# SAMC21_Xplained_Pro_Arduino_Connectors.net
KiCad netlist of a schematic drawn in Altium Designer
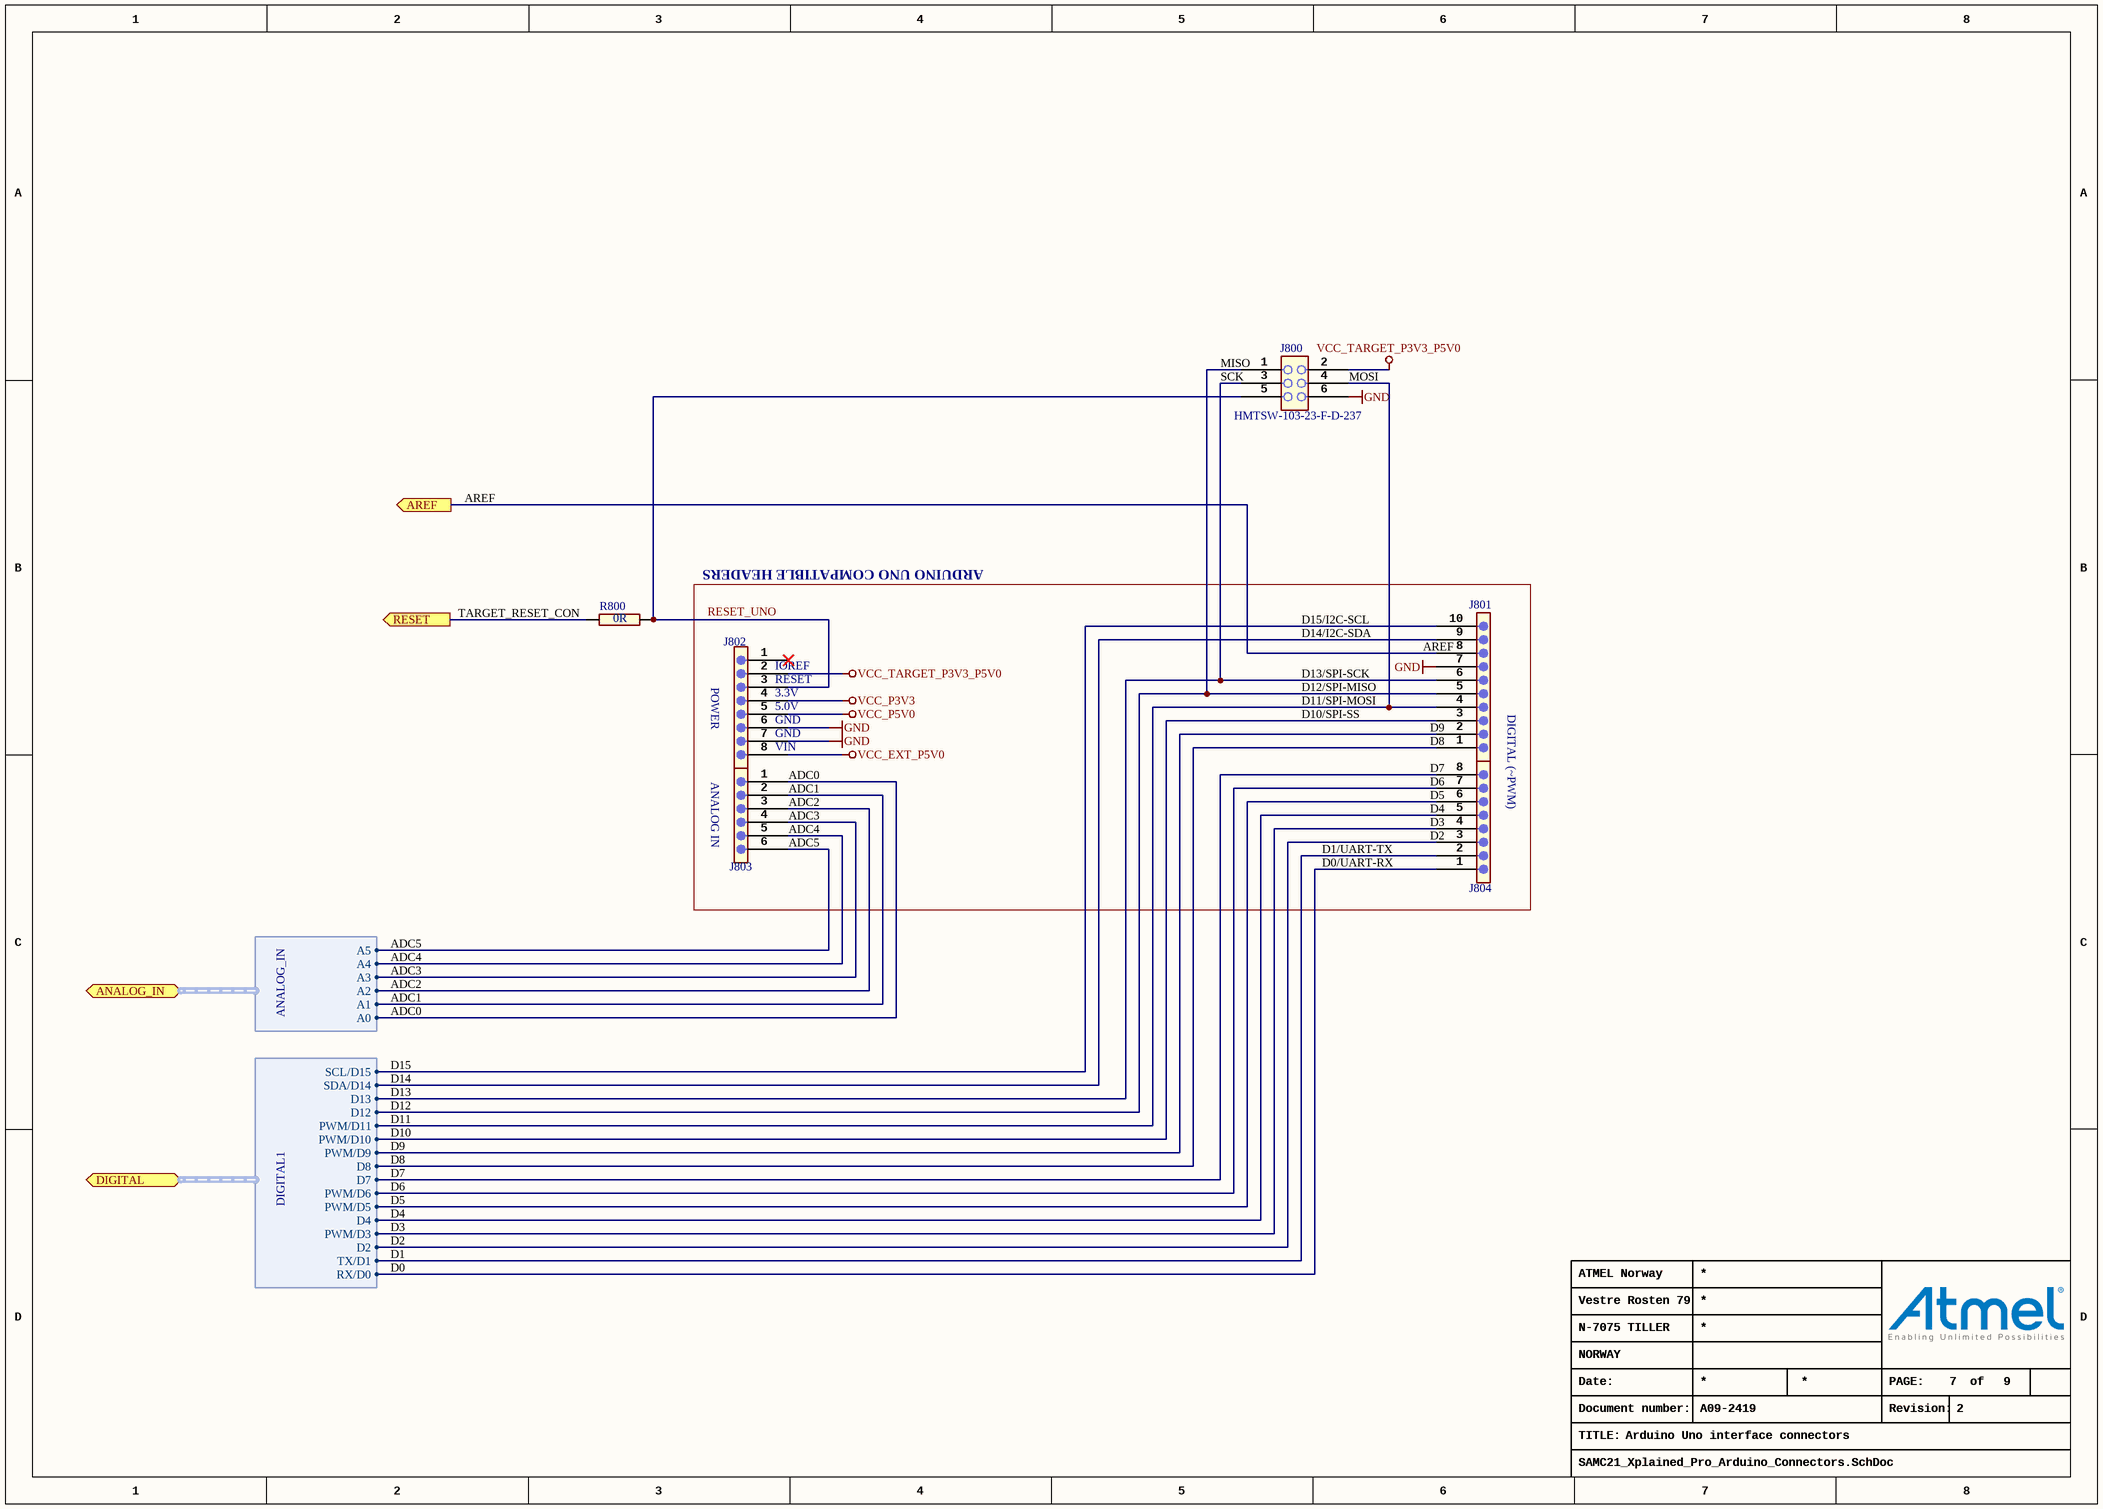
[diagram p0: SAMC21_Xplained_Pro_Arduino_Connectors.SchDoc]

(export (version "E")
  (design (tool "Eeschema 10.0.6"))
  (components
    (comp (ref "J800")
      (value "HMTSW-103-23-F-D-237")
      (footprint "AP8-00182")
      (description "2x3 pin header, 2.54mm pitch, Pin-in-Paste THM")
      (fields (field (name "MANUFACTURER") "SAMTEC") (field (name "Comment") "HEADER 2x3"))
      (libsource (lib "AltiumDbLib") (part "HEADER 2x3"))
    )
    (comp (ref "J801")
      (value "HEADER 1x10 FEMALE")
      (footprint "AP8-00822")
      (description "1x10 receptacle pin header, low insertion force, 2.54mm pitch THM, Pin in Paste")
      (fields (field (name "MANUFACTURER") "SAMTEC") (field (name "MPN") "SSQ-110-21-F-S"))
      (libsource (lib "AltiumDbLib") (part "HEADER 1x10 FEMALE"))
    )
    (comp (ref "J802")
      (value "HEADER 1x8 FEMALE")
      (footprint "AP8-00823")
      (description "1x8 receptacle pin header, low insertion force, 2.54mm pitch THM, Pin in Paste")
      (fields (field (name "MANUFACTURER") "SAMTEC") (field (name "MPN") "SSQ-108-21-F-S"))
      (libsource (lib "AltiumDbLib") (part "HEADER 1x8 FEMALE"))
    )
    (comp (ref "J803")
      (value "HEADER 1x6 FEMALE")
      (footprint "AP8-00824")
      (description "1x6 receptacle pin header, low insertion force, 2.54mm pitch THM")
      (fields (field (name "MANUFACTURER") "SAMTEC") (field (name "MPN") "SSQ-106-21-F-S"))
      (libsource (lib "AltiumDbLib") (part "HEADER 1x6 FEMALE"))
    )
    (comp (ref "J804")
      (value "HEADER 1x8 FEMALE")
      (footprint "AP8-00823")
      (description "1x8 receptacle pin header, low insertion force, 2.54mm pitch THM, Pin in Paste")
      (fields (field (name "MANUFACTURER") "SAMTEC") (field (name "MPN") "SSQ-108-21-F-S"))
      (libsource (lib "") (part "HEADER 1x8 FEMALE_1"))
    )
    (comp (ref "R800")
      (value "0R")
      (footprint "AP2-00000")
      (description "RES 0.0 OHM 1/16W 0402 SMD")
      (fields (field (name "TOLERANCE") "1 %") (field (name "MANUFACTURER") "(n/a)"))
      (libsource (lib "AltiumDbLib") (part "R2"))
    )
  )
  (nets
    (net (code "3") (name "/A0") (class "Default")
      (node (ref "J803") (pin "1") (pinfunction "1_1") (pintype "passive"))
    )
    (net (code "4") (name "/A1") (class "Default")
      (node (ref "J803") (pin "2") (pinfunction "2_2") (pintype "passive"))
    )
    (net (code "5") (name "/A2") (class "Default")
      (node (ref "J803") (pin "3") (pinfunction "3_3") (pintype "passive"))
    )
    (net (code "6") (name "/A3") (class "Default")
      (node (ref "J803") (pin "4") (pinfunction "4_4") (pintype "passive"))
    )
    (net (code "7") (name "/A4") (class "Default")
      (node (ref "J803") (pin "5") (pinfunction "5_5") (pintype "passive"))
    )
    (net (code "8") (name "/A5") (class "Default")
      (node (ref "J803") (pin "6") (pinfunction "6_6") (pintype "passive"))
    )
    (net (code "9") (name "/AREF") (class "Default")
      (node (ref "J801") (pin "8") (pinfunction "8_8") (pintype "passive"))
    )
    (net (code "10") (name "/D2") (class "Default")
      (node (ref "J804") (pin "3") (pinfunction "3_3") (pintype "passive"))
    )
    (net (code "11") (name "/D4") (class "Default")
      (node (ref "J804") (pin "5") (pinfunction "5_5") (pintype "passive"))
    )
    (net (code "12") (name "/D7") (class "Default")
      (node (ref "J804") (pin "8") (pinfunction "8_8") (pintype "passive"))
    )
    (net (code "13") (name "/D8") (class "Default")
      (node (ref "J801") (pin "1") (pinfunction "1_1") (pintype "passive"))
    )
    (net (code "14") (name "/D12") (class "Default")
      (node (ref "J800") (pin "1") (pinfunction "1_1") (pintype "passive"))
      (node (ref "J801") (pin "5") (pinfunction "5_5") (pintype "passive"))
    )
    (net (code "15") (name "/D13") (class "Default")
      (node (ref "J800") (pin "3") (pinfunction "3_3") (pintype "passive"))
      (node (ref "J801") (pin "6") (pinfunction "6_6") (pintype "passive"))
    )
    (net (code "16") (name "/PWM{slash}D3") (class "Default")
      (node (ref "J804") (pin "4") (pinfunction "4_4") (pintype "passive"))
    )
    (net (code "17") (name "/PWM{slash}D5") (class "Default")
      (node (ref "J804") (pin "6") (pinfunction "6_6") (pintype "passive"))
    )
    (net (code "18") (name "/PWM{slash}D6") (class "Default")
      (node (ref "J804") (pin "7") (pinfunction "7_7") (pintype "passive"))
    )
    (net (code "19") (name "/PWM{slash}D9") (class "Default")
      (node (ref "J801") (pin "2") (pinfunction "2_2") (pintype "passive"))
    )
    (net (code "20") (name "/PWM{slash}D10") (class "Default")
      (node (ref "J801") (pin "3") (pinfunction "3_3") (pintype "passive"))
    )
    (net (code "21") (name "/PWM{slash}D11") (class "Default")
      (node (ref "J800") (pin "4") (pinfunction "4_4") (pintype "passive"))
      (node (ref "J801") (pin "4") (pinfunction "4_4") (pintype "passive"))
    )
    (net (code "22") (name "/RESET") (class "Default")
      (node (ref "R800") (pin "1") (pinfunction "1_1") (pintype "passive"))
    )
    (net (code "23") (name "/RESET_UNO") (class "Default")
      (node (ref "J800") (pin "5") (pinfunction "5_5") (pintype "passive"))
      (node (ref "J802") (pin "3") (pinfunction "3_3") (pintype "passive"))
      (node (ref "R800") (pin "2") (pinfunction "2_2") (pintype "passive"))
    )
    (net (code "24") (name "/RX{slash}D0") (class "Default")
      (node (ref "J804") (pin "1") (pinfunction "1_1") (pintype "passive"))
    )
    (net (code "25") (name "/SCL{slash}D15") (class "Default")
      (node (ref "J801") (pin "10") (pinfunction "10_10") (pintype "passive"))
    )
    (net (code "26") (name "/SDA{slash}D14") (class "Default")
      (node (ref "J801") (pin "9") (pinfunction "9_9") (pintype "passive"))
    )
    (net (code "27") (name "/TX{slash}D1") (class "Default")
      (node (ref "J804") (pin "2") (pinfunction "2_2") (pintype "passive"))
    )
    (net (code "30") (name "GND") (class "Default")
      (node (ref "J800") (pin "6") (pinfunction "6_6") (pintype "passive"))
      (node (ref "J801") (pin "7") (pinfunction "7_7") (pintype "passive"))
      (node (ref "J802") (pin "6") (pinfunction "6_6") (pintype "passive"))
      (node (ref "J802") (pin "7") (pinfunction "7_7") (pintype "passive"))
    )
    (net (code "31") (name "VCC_EXT_P5V0") (class "Default")
      (node (ref "J802") (pin "8") (pinfunction "8_8") (pintype "passive"))
    )
    (net (code "32") (name "VCC_P3V3") (class "Default")
      (node (ref "J802") (pin "4") (pinfunction "4_4") (pintype "passive"))
    )
    (net (code "33") (name "VCC_P5V0") (class "Default")
      (node (ref "J802") (pin "5") (pinfunction "5_5") (pintype "passive"))
    )
    (net (code "34") (name "VCC_TARGET_P3V3_P5V0") (class "Default")
      (node (ref "J800") (pin "2") (pinfunction "2_2") (pintype "passive"))
      (node (ref "J802") (pin "2") (pinfunction "2_2") (pintype "passive"))
    )
    (net (code "35") (name "unconnected-(J802-Pad1)") (class "Default")
      (node (ref "J802") (pin "1") (pinfunction "1_1") (pintype "passive+no_connect"))
    )
  )
)
